# Power_ICs.net
KiCad netlist of a schematic drawn in Altium Designer
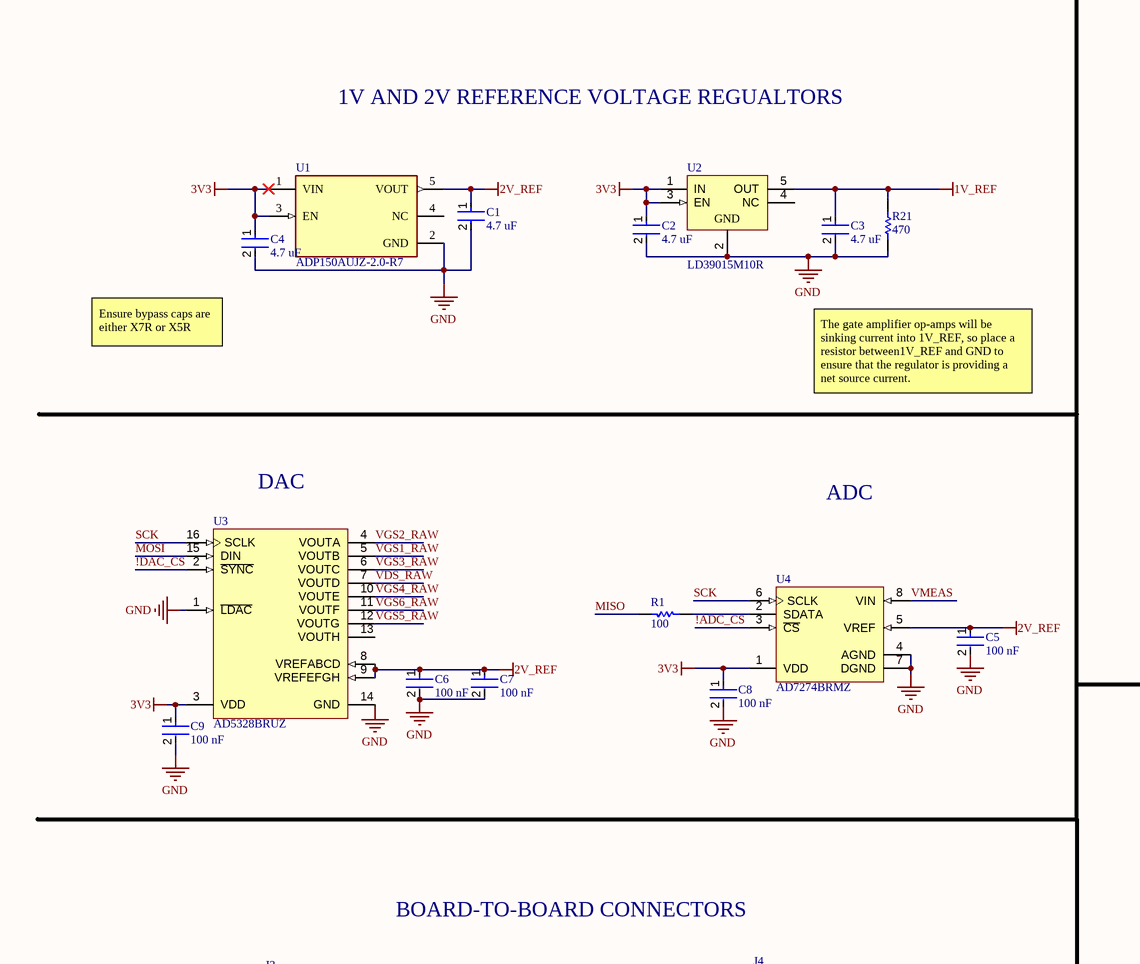
[diagram p0: Power+ICs.SchDoc, top left]
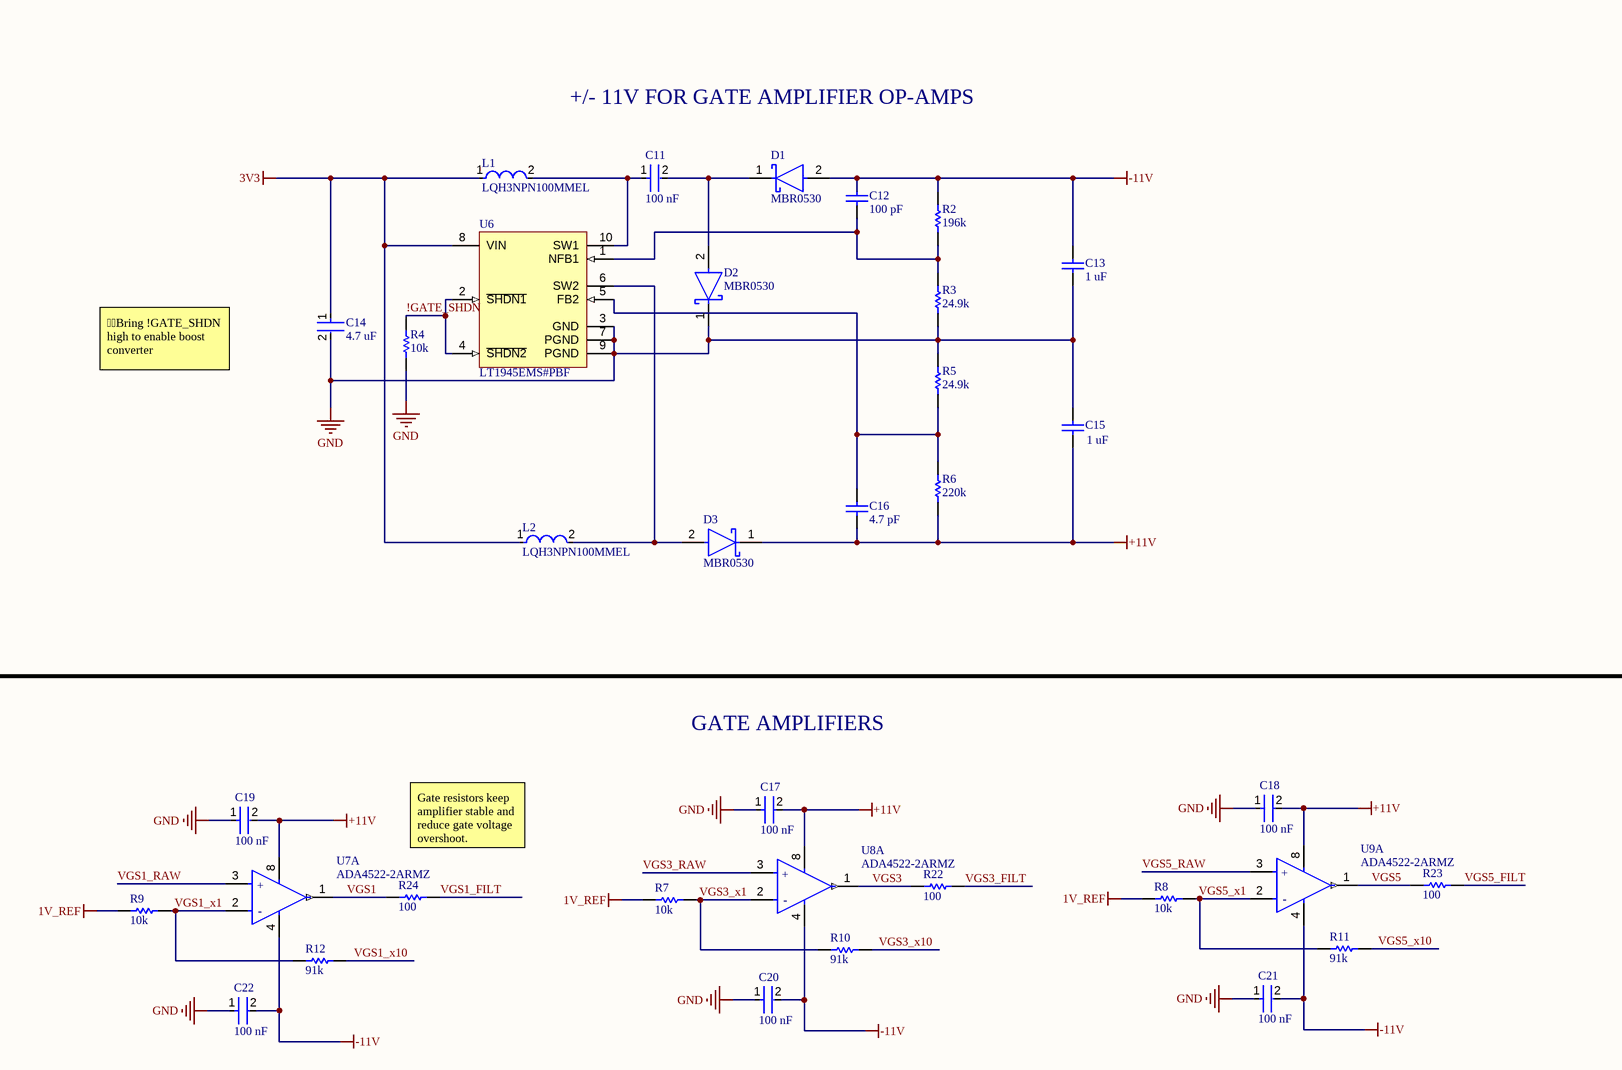
[diagram p1: Power+ICs.SchDoc, top right]
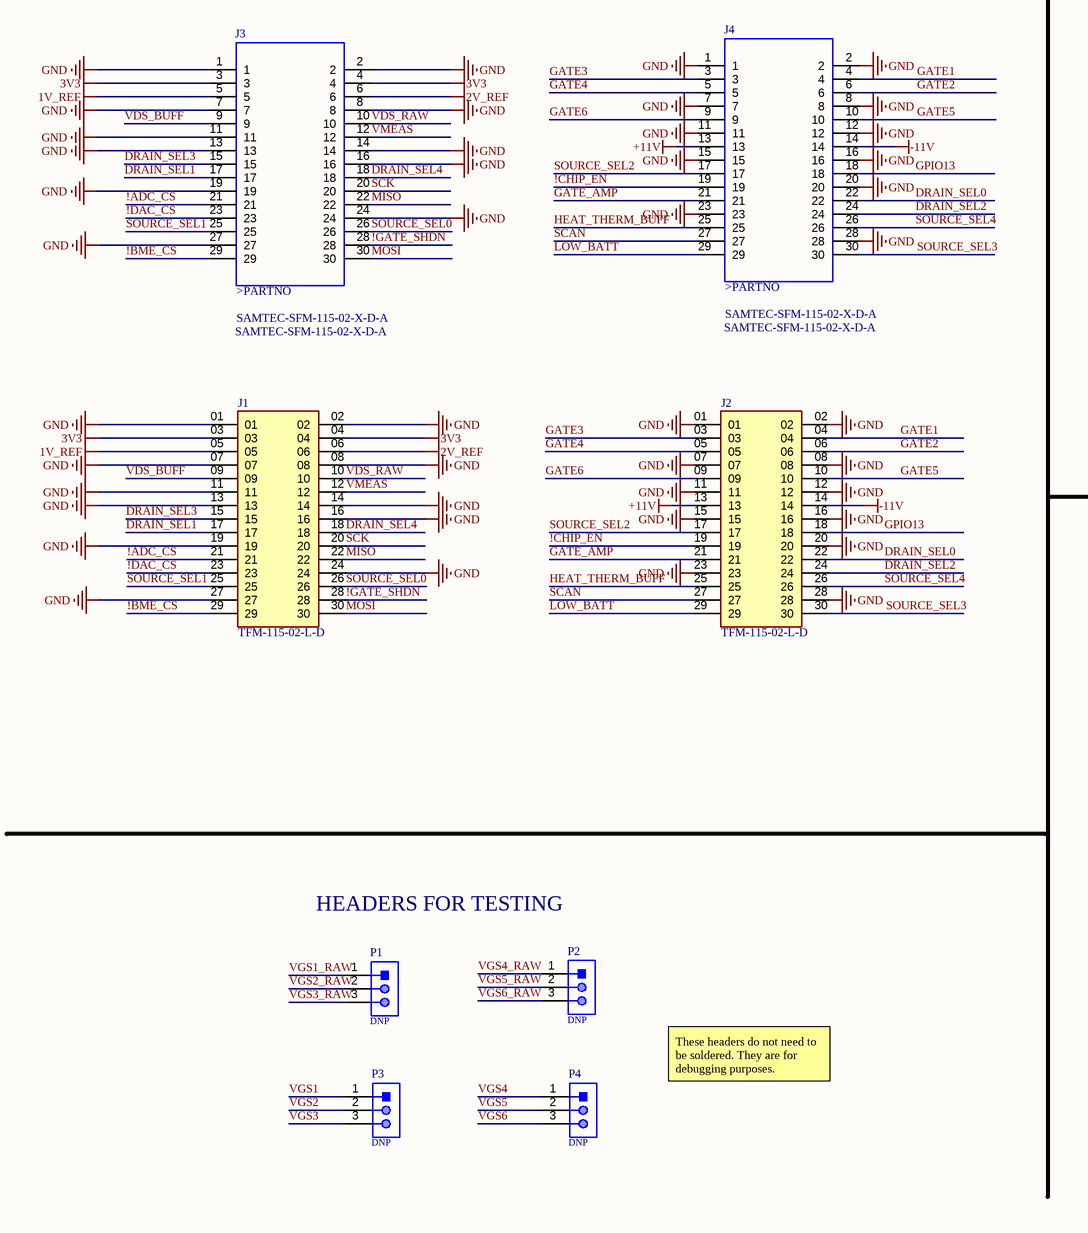
[diagram p2: Power+ICs.SchDoc, bottom left]
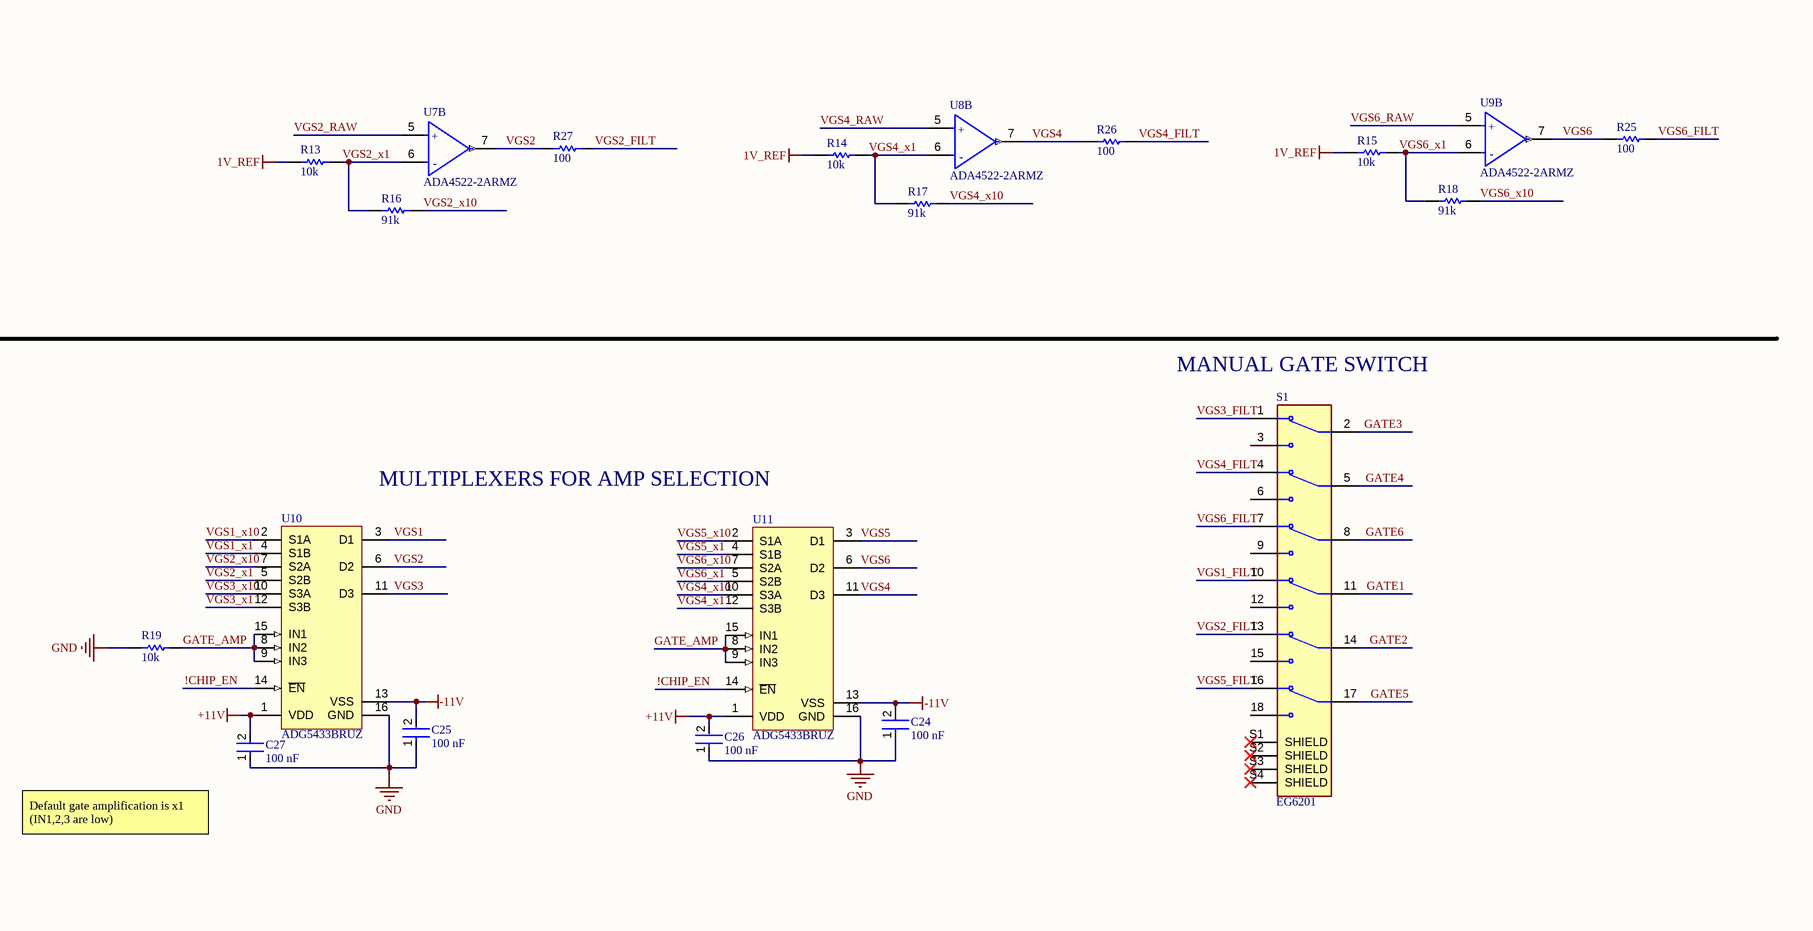
[diagram p3: Power+ICs.SchDoc, bottom right]

(export (version "E")
  (design (tool "Eeschema 10.0.6"))
  (components
    (comp (ref "C1")
      (value "4.7 uF")
      (footprint "FP-C0805C475K3PACTU-MFG")
      (description "CAP CER 4.7UF 25V X5R 0805")
      (fields (field (name "TOLERANCE") "10%") (field (name "VOLTAGE") "25V"))
      (libsource (lib "Altium Content Vault") (part "02cd4be3c70576c341d710602a673aa"))
    )
    (comp (ref "C2")
      (value "4.7 uF")
      (footprint "FP-C0805C475K3PACTU-MFG")
      (description "CAP CER 4.7UF 25V X5R 0805")
      (fields (field (name "TOLERANCE") "10%") (field (name "VOLTAGE") "25V"))
      (libsource (lib "Altium Content Vault") (part "02cd4be3c70576c341d710602a673aa"))
    )
    (comp (ref "C3")
      (value "4.7 uF")
      (footprint "FP-C0805C475K3PACTU-MFG")
      (description "CAP CER 4.7UF 25V X5R 0805")
      (fields (field (name "TOLERANCE") "10%") (field (name "VOLTAGE") "25V"))
      (libsource (lib "Altium Content Vault") (part "02cd4be3c70576c341d710602a673aa"))
    )
    (comp (ref "C4")
      (value "4.7 uF")
      (footprint "FP-C0805C475K3PACTU-MFG")
      (description "CAP CER 4.7UF 25V X5R 0805")
      (fields (field (name "TOLERANCE") "10%") (field (name "VOLTAGE") "25V"))
      (libsource (lib "Altium Content Vault") (part "02cd4be3c70576c341d710602a673aa"))
    )
    (comp (ref "C5")
      (value "100 nF")
      (footprint "FP-C0805C-DN-MFG")
      (description "CAP CER 0.1UF 50V X7R 0805")
      (fields
        (field (name "MANUFACTURER PART NUMBER") "C0805C104K5RACTU")
        (field (name "MANUFACTURER") "KEMET")
      )
      (libsource (lib "Altium Content Vault") (part "b4654b650e69147ec39a6b967a45e02"))
    )
    (comp (ref "C6")
      (value "100 nF")
      (footprint "FP-C0805C-DN-MFG")
      (description "CAP CER 0.1UF 50V X7R 0805")
      (fields
        (field (name "MANUFACTURER PART NUMBER") "C0805C104K5RACTU")
        (field (name "MANUFACTURER") "KEMET")
      )
      (libsource (lib "Altium Content Vault") (part "b4654b650e69147ec39a6b967a45e02"))
    )
    (comp (ref "C7")
      (value "100 nF")
      (footprint "FP-C0805C-DN-MFG")
      (description "CAP CER 0.1UF 50V X7R 0805")
      (fields
        (field (name "MANUFACTURER PART NUMBER") "C0805C104K5RACTU")
        (field (name "MANUFACTURER") "KEMET")
      )
      (libsource (lib "Altium Content Vault") (part "b4654b650e69147ec39a6b967a45e02"))
    )
    (comp (ref "C8")
      (value "100 nF")
      (footprint "FP-C0805C-DN-MFG")
      (description "CAP CER 0.1UF 50V X7R 0805")
      (fields
        (field (name "MANUFACTURER PART NUMBER") "C0805C104K5RACTU")
        (field (name "MANUFACTURER") "KEMET")
      )
      (libsource (lib "Altium Content Vault") (part "b4654b650e69147ec39a6b967a45e02"))
    )
    (comp (ref "C9")
      (value "100 nF")
      (footprint "FP-C0805C-DN-MFG")
      (description "CAP CER 0.1UF 50V X7R 0805")
      (fields
        (field (name "MANUFACTURER PART NUMBER") "C0805C104K5RACTU")
        (field (name "MANUFACTURER") "KEMET")
      )
      (libsource (lib "Altium Content Vault") (part "b4654b650e69147ec39a6b967a45e02"))
    )
    (comp (ref "C11")
      (value "100 nF")
      (footprint "FP-C0805C-DN-MFG")
      (description "CAP CER 0.1UF 50V X7R 0805")
      (fields
        (field (name "MANUFACTURER PART NUMBER") "C0805C104K5RACTU")
        (field (name "MANUFACTURER") "KEMET")
      )
      (libsource (lib "Altium Content Vault") (part "b4654b650e69147ec39a6b967a45e02"))
    )
    (comp (ref "C12")
      (value "100 pF")
      (footprint "CAPC2013X140X50ML20T25")
      (description "08055C101KAT2A")
      (fields (field (name "MANUFACTURER") "AVX Interconnect / Elco"))
      (libsource (lib "Altium Content Vault") (part "CAP"))
    )
    (comp (ref "C13")
      (value "1 uF")
      (footprint "CAPC3216X110X50LL20T25")
      (description "C1206C105K5RACTU")
      (fields (field (name "MANUFACTURER") "Kemet") (field (name "TOLERANCE") "10%"))
      (libsource (lib "Altium Content Vault") (part "CAP-NP-2"))
    )
    (comp (ref "C14")
      (value "4.7 uF")
      (footprint "FP-C0805C475K3PACTU-MFG")
      (description "CAP CER 4.7UF 25V X5R 0805")
      (fields (field (name "TOLERANCE") "10%") (field (name "VOLTAGE") "25V"))
      (libsource (lib "Altium Content Vault") (part "02cd4be3c70576c341d710602a673aa"))
    )
    (comp (ref "C15")
      (value "1 uF")
      (footprint "CAPC3216X110X50LL20T25")
      (description "C1206C105K5RACTU")
      (fields (field (name "MANUFACTURER") "Kemet") (field (name "TOLERANCE") "10%"))
      (libsource (lib "Altium Content Vault") (part "CAP-NP-2"))
    )
    (comp (ref "C16")
      (value "4.7 pF")
      (footprint "CAPC2013X71X50ML20T25")
      (description "08055A4R7CAT2A")
      (fields (field (name "MANUFACTURER") "AVX Interconnect / Elco"))
      (libsource (lib "Altium Content Vault") (part "CAP"))
    )
    (comp (ref "C17")
      (value "100 nF")
      (footprint "FP-C0805C-DN-MFG")
      (description "CAP CER 0.1UF 50V X7R 0805")
      (fields
        (field (name "MANUFACTURER PART NUMBER") "C0805C104K5RACTU")
        (field (name "MANUFACTURER") "KEMET")
      )
      (libsource (lib "Altium Content Vault") (part "b4654b650e69147ec39a6b967a45e02"))
    )
    (comp (ref "C18")
      (value "100 nF")
      (footprint "FP-C0805C-DN-MFG")
      (description "CAP CER 0.1UF 50V X7R 0805")
      (fields
        (field (name "MANUFACTURER PART NUMBER") "C0805C104K5RACTU")
        (field (name "MANUFACTURER") "KEMET")
      )
      (libsource (lib "Altium Content Vault") (part "b4654b650e69147ec39a6b967a45e02"))
    )
    (comp (ref "C19")
      (value "100 nF")
      (footprint "FP-C0805C-DN-MFG")
      (description "CAP CER 0.1UF 50V X7R 0805")
      (fields
        (field (name "MANUFACTURER PART NUMBER") "C0805C104K5RACTU")
        (field (name "MANUFACTURER") "KEMET")
      )
      (libsource (lib "Altium Content Vault") (part "b4654b650e69147ec39a6b967a45e02"))
    )
    (comp (ref "C20")
      (value "100 nF")
      (footprint "FP-C0805C-DN-MFG")
      (description "CAP CER 0.1UF 50V X7R 0805")
      (fields
        (field (name "MANUFACTURER PART NUMBER") "C0805C104K5RACTU")
        (field (name "MANUFACTURER") "KEMET")
      )
      (libsource (lib "Altium Content Vault") (part "b4654b650e69147ec39a6b967a45e02"))
    )
    (comp (ref "C21")
      (value "100 nF")
      (footprint "FP-C0805C-DN-MFG")
      (description "CAP CER 0.1UF 50V X7R 0805")
      (fields
        (field (name "MANUFACTURER PART NUMBER") "C0805C104K5RACTU")
        (field (name "MANUFACTURER") "KEMET")
      )
      (libsource (lib "Altium Content Vault") (part "b4654b650e69147ec39a6b967a45e02"))
    )
    (comp (ref "C22")
      (value "100 nF")
      (footprint "FP-C0805C-DN-MFG")
      (description "CAP CER 0.1UF 50V X7R 0805")
      (fields
        (field (name "MANUFACTURER PART NUMBER") "C0805C104K5RACTU")
        (field (name "MANUFACTURER") "KEMET")
      )
      (libsource (lib "Altium Content Vault") (part "b4654b650e69147ec39a6b967a45e02"))
    )
    (comp (ref "C24")
      (value "100 nF")
      (footprint "FP-C0805C-DN-MFG")
      (description "CAP CER 0.1UF 50V X7R 0805")
      (fields
        (field (name "MANUFACTURER PART NUMBER") "C0805C104K5RACTU")
        (field (name "MANUFACTURER") "KEMET")
      )
      (libsource (lib "Altium Content Vault") (part "b4654b650e69147ec39a6b967a45e02"))
    )
    (comp (ref "C25")
      (value "100 nF")
      (footprint "FP-C0805C-DN-MFG")
      (description "CAP CER 0.1UF 50V X7R 0805")
      (fields
        (field (name "MANUFACTURER PART NUMBER") "C0805C104K5RACTU")
        (field (name "MANUFACTURER") "KEMET")
      )
      (libsource (lib "Altium Content Vault") (part "b4654b650e69147ec39a6b967a45e02"))
    )
    (comp (ref "C26")
      (value "100 nF")
      (footprint "FP-C0805C-DN-MFG")
      (description "CAP CER 0.1UF 50V X7R 0805")
      (fields
        (field (name "MANUFACTURER PART NUMBER") "C0805C104K5RACTU")
        (field (name "MANUFACTURER") "KEMET")
      )
      (libsource (lib "Altium Content Vault") (part "b4654b650e69147ec39a6b967a45e02"))
    )
    (comp (ref "C27")
      (value "100 nF")
      (footprint "FP-C0805C-DN-MFG")
      (description "CAP CER 0.1UF 50V X7R 0805")
      (fields
        (field (name "MANUFACTURER PART NUMBER") "C0805C104K5RACTU")
        (field (name "MANUFACTURER") "KEMET")
      )
      (libsource (lib "Altium Content Vault") (part "b4654b650e69147ec39a6b967a45e02"))
    )
    (comp (ref "D1")
      (value "MBR0530")
      (footprint "FP-425-04-MFG")
      (description "DIODE SCHOTTKY 30V 500MA SOD123")
      (libsource (lib "Altium Content Vault") (part "1d6ec82d83fb6aee721767c19dac4b9"))
    )
    (comp (ref "D2")
      (value "MBR0530")
      (footprint "FP-425-04-MFG")
      (description "DIODE SCHOTTKY 30V 500MA SOD123")
      (libsource (lib "Altium Content Vault") (part "1d6ec82d83fb6aee721767c19dac4b9"))
    )
    (comp (ref "D3")
      (value "MBR0530")
      (footprint "FP-425-04-MFG")
      (description "DIODE SCHOTTKY 30V 500MA SOD123")
      (libsource (lib "Altium Content Vault") (part "1d6ec82d83fb6aee721767c19dac4b9"))
    )
    (comp (ref "J1")
      (value "TFM-115-02-L-D")
      (footprint "SAMTEC_TFM-115-02-L-D:SAMTEC_TFM-115-02-L-D")
      (fields (field (name "MF") "Samtec Inc."))
      (libsource (lib "TFM-115-02-L-D") (part "TFM-115-02-L-D"))
    )
    (comp (ref "J2")
      (value "TFM-115-02-L-D")
      (footprint "SAMTEC_TFM-115-02-L-D:SAMTEC_TFM-115-02-L-D")
      (fields (field (name "MF") "Samtec Inc."))
      (libsource (lib "TFM-115-02-L-D") (part "TFM-115-02-L-D"))
    )
    (comp (ref "J3")
      (value "SAMTEC-SFM-115-02-X-D-A")
      (footprint "SAMTEC-SFM-115-02-X-D-A:SAMTEC-SFM-115-02-X-D-A")
      (fields (field (name "MF") "Samtec Inc."))
      (libsource (lib "SAMTEC-SFM-115-02-X-D-A") (part "SAMTEC-SFM-115-02-X-D-A"))
    )
    (comp (ref "J4")
      (value "SAMTEC-SFM-115-02-X-D-A")
      (footprint "SAMTEC-SFM-115-02-X-D-A:SAMTEC-SFM-115-02-X-D-A")
      (fields (field (name "MF") "Samtec Inc."))
      (libsource (lib "SAMTEC-SFM-115-02-X-D-A") (part "SAMTEC-SFM-115-02-X-D-A"))
    )
    (comp (ref "L1")
      (value "LQH3NPN100MMEL")
      (footprint "FP-LQH3NPH_ME-MFG")
      (description "Wire Wound Ferrite Inductor for Power Lines 10μH ±20% 0.228Ω 1280mA 1212")
      (fields (field (name "TOLERANCE") "20%"))
      (libsource (lib "Altium Content Vault") (part "725321dda6339637d4d059423bc1c3c"))
    )
    (comp (ref "L2")
      (value "LQH3NPN100MMEL")
      (footprint "FP-LQH3NPH_ME-MFG")
      (description "Wire Wound Ferrite Inductor for Power Lines 10μH ±20% 0.228Ω 1280mA 1212")
      (fields (field (name "TOLERANCE") "20%"))
      (libsource (lib "Altium Content Vault") (part "725321dda6339637d4d059423bc1c3c"))
    )
    (comp (ref "P1")
      (value "DNP")
      (footprint "61300311021")
      (description "THT Angled Pin Header WR-PHD, Pitch 2.54 mm, Single Row, 3 pins")
      (fields
        (field (name "PART NUMBER") "61300311021")
        (field (name "MANUFACTURER") "Wurth Elektronik")
        (field (name "PUBLISHER") "WurthElektronik")
      )
      (libsource (lib "Altium Content Vault") (part "WE-CN-1P-M-R3"))
    )
    (comp (ref "P2")
      (value "DNP")
      (footprint "61300311021")
      (description "THT Angled Pin Header WR-PHD, Pitch 2.54 mm, Single Row, 3 pins")
      (fields
        (field (name "PART NUMBER") "61300311021")
        (field (name "MANUFACTURER") "Wurth Elektronik")
        (field (name "PUBLISHER") "WurthElektronik")
      )
      (libsource (lib "Altium Content Vault") (part "WE-CN-1P-M-R3"))
    )
    (comp (ref "P3")
      (value "DNP")
      (footprint "61300311021")
      (description "THT Angled Pin Header WR-PHD, Pitch 2.54 mm, Single Row, 3 pins")
      (fields
        (field (name "PART NUMBER") "61300311021")
        (field (name "MANUFACTURER") "Wurth Elektronik")
        (field (name "PUBLISHER") "WurthElektronik")
      )
      (libsource (lib "Altium Content Vault") (part "WE-CN-1P-M-R3"))
    )
    (comp (ref "P4")
      (value "DNP")
      (footprint "61300311021")
      (description "THT Angled Pin Header WR-PHD, Pitch 2.54 mm, Single Row, 3 pins")
      (fields
        (field (name "PART NUMBER") "61300311021")
        (field (name "MANUFACTURER") "Wurth Elektronik")
        (field (name "PUBLISHER") "WurthElektronik")
      )
      (libsource (lib "Altium Content Vault") (part "WE-CN-1P-M-R3"))
    )
    (comp (ref "R1")
      (value "100")
      (footprint "RESC2013X50X30LL20T20")
      (fields (field (name "MANUFACTURER") "Vishay Dale") (field (name "PART NUMBER") "CRCW0805100RFKEA"))
      (libsource (lib "Altium Content Vault") (part "RES"))
    )
    (comp (ref "R2")
      (value "196k")
      (footprint "RESC2013X50X30LL20T20")
      (fields (field (name "MANUFACTURER") "Vishay Dale") (field (name "PART NUMBER") "CRCW0805196KFKEA"))
      (libsource (lib "Altium Content Vault") (part "RES"))
    )
    (comp (ref "R3")
      (value "24.9k")
      (footprint "RESC2013X70X40LL20T20")
      (fields (field (name "PART NUMBER") "ERJ-6ENF2492V") (field (name "MANUFACTURER") "Panasonic"))
      (libsource (lib "Altium Content Vault") (part "RES"))
    )
    (comp (ref "R4")
      (value "10k")
      (footprint "RESC2013X60X35NL10T20")
      (description "Chip Resistor, 10 KOhm, +/- 1%, 0.125 W, -55 to 155 degC, 0805 (2012 Metric), RoHS, Tape and Reel")
      (fields (field (name "MANUFACTURER") "Yageo"))
      (libsource (lib "Altium Content Vault") (part "RES-2"))
    )
    (comp (ref "R5")
      (value "24.9k")
      (footprint "RESC2013X70X40LL20T20")
      (fields (field (name "PART NUMBER") "ERJ-6ENF2492V") (field (name "MANUFACTURER") "Panasonic"))
      (libsource (lib "Altium Content Vault") (part "RES"))
    )
    (comp (ref "R6")
      (value "220k")
      (footprint "RESC2013X70X40ML20T20")
      (fields (field (name "PART NUMBER") "ERJ6ENF2203V") (field (name "MANUFACTURER") "Panasonic"))
      (libsource (lib "Altium Content Vault") (part "RES"))
    )
    (comp (ref "R7")
      (value "10k")
      (footprint "RESC2013X60X35NL10T20")
      (description "Chip Resistor, 10 KOhm, +/- 1%, 0.125 W, -55 to 155 degC, 0805 (2012 Metric), RoHS, Tape and Reel")
      (fields (field (name "MANUFACTURER") "Yageo"))
      (libsource (lib "Altium Content Vault") (part "RES-2"))
    )
    (comp (ref "R8")
      (value "10k")
      (footprint "RESC2013X60X35NL10T20")
      (description "Chip Resistor, 10 KOhm, +/- 1%, 0.125 W, -55 to 155 degC, 0805 (2012 Metric), RoHS, Tape and Reel")
      (fields (field (name "MANUFACTURER") "Yageo"))
      (libsource (lib "Altium Content Vault") (part "RES-2"))
    )
    (comp (ref "R9")
      (value "10k")
      (footprint "RESC2013X60X35NL10T20")
      (description "Chip Resistor, 10 KOhm, +/- 1%, 0.125 W, -55 to 155 degC, 0805 (2012 Metric), RoHS, Tape and Reel")
      (fields (field (name "MANUFACTURER") "Yageo"))
      (libsource (lib "Altium Content Vault") (part "RES-2"))
    )
    (comp (ref "R10")
      (value "91k")
      (footprint "RESC2013X60X35ML10T20")
      (fields (field (name "PART NUMBER") "RC0805JR-0791KL") (field (name "MANUFACTURER") "Yageo"))
      (libsource (lib "Altium Content Vault") (part "RES"))
    )
    (comp (ref "R11")
      (value "91k")
      (footprint "RESC2013X60X35ML10T20")
      (fields (field (name "PART NUMBER") "RC0805JR-0791KL") (field (name "MANUFACTURER") "Yageo"))
      (libsource (lib "Altium Content Vault") (part "RES"))
    )
    (comp (ref "R12")
      (value "91k")
      (footprint "RESC2013X60X35ML10T20")
      (fields (field (name "PART NUMBER") "RC0805JR-0791KL") (field (name "MANUFACTURER") "Yageo"))
      (libsource (lib "Altium Content Vault") (part "RES"))
    )
    (comp (ref "R13")
      (value "10k")
      (footprint "RESC2013X60X35NL10T20")
      (description "Chip Resistor, 10 KOhm, +/- 1%, 0.125 W, -55 to 155 degC, 0805 (2012 Metric), RoHS, Tape and Reel")
      (fields (field (name "MANUFACTURER") "Yageo"))
      (libsource (lib "Altium Content Vault") (part "RES-2"))
    )
    (comp (ref "R14")
      (value "10k")
      (footprint "RESC2013X60X35NL10T20")
      (description "Chip Resistor, 10 KOhm, +/- 1%, 0.125 W, -55 to 155 degC, 0805 (2012 Metric), RoHS, Tape and Reel")
      (fields (field (name "MANUFACTURER") "Yageo"))
      (libsource (lib "Altium Content Vault") (part "RES-2"))
    )
    (comp (ref "R15")
      (value "10k")
      (footprint "RESC2013X60X35NL10T20")
      (description "Chip Resistor, 10 KOhm, +/- 1%, 0.125 W, -55 to 155 degC, 0805 (2012 Metric), RoHS, Tape and Reel")
      (fields (field (name "MANUFACTURER") "Yageo"))
      (libsource (lib "Altium Content Vault") (part "RES-2"))
    )
    (comp (ref "R16")
      (value "91k")
      (footprint "RESC2013X60X35ML10T20")
      (fields (field (name "PART NUMBER") "RC0805JR-0791KL") (field (name "MANUFACTURER") "Yageo"))
      (libsource (lib "Altium Content Vault") (part "RES"))
    )
    (comp (ref "R17")
      (value "91k")
      (footprint "RESC2013X60X35ML10T20")
      (fields (field (name "PART NUMBER") "RC0805JR-0791KL") (field (name "MANUFACTURER") "Yageo"))
      (libsource (lib "Altium Content Vault") (part "RES"))
    )
    (comp (ref "R18")
      (value "91k")
      (footprint "RESC2013X60X35ML10T20")
      (fields (field (name "PART NUMBER") "RC0805JR-0791KL") (field (name "MANUFACTURER") "Yageo"))
      (libsource (lib "Altium Content Vault") (part "RES"))
    )
    (comp (ref "R19")
      (value "10k")
      (footprint "RESC2013X60X35NL10T20")
      (description "Chip Resistor, 10 KOhm, +/- 1%, 0.125 W, -55 to 155 degC, 0805 (2012 Metric), RoHS, Tape and Reel")
      (fields (field (name "MANUFACTURER") "Yageo"))
      (libsource (lib "Altium Content Vault") (part "RES-2"))
    )
    (comp (ref "R21")
      (value "470")
      (footprint "RESC2013X70X40ML20T20")
      (description "Chip Resistor, 470 Ohm, +/- 1%, 0.125 W, -55 to 155 degC, 0805 (2012 Metric), RoHS, Tape and Reel")
      (fields (field (name "MANUFACTURER") "Panasonic"))
      (libsource (lib "Altium Content Vault") (part "RES-2"))
    )
    (comp (ref "R22")
      (value "100")
      (footprint "RESC2013X50X30LL20T20")
      (fields (field (name "MANUFACTURER") "Vishay Dale") (field (name "PART NUMBER") "CRCW0805100RFKEA"))
      (libsource (lib "Altium Content Vault") (part "RES"))
    )
    (comp (ref "R23")
      (value "100")
      (footprint "RESC2013X50X30LL20T20")
      (fields (field (name "MANUFACTURER") "Vishay Dale") (field (name "PART NUMBER") "CRCW0805100RFKEA"))
      (libsource (lib "Altium Content Vault") (part "RES"))
    )
    (comp (ref "R24")
      (value "100")
      (footprint "RESC2013X50X30LL20T20")
      (fields (field (name "MANUFACTURER") "Vishay Dale") (field (name "PART NUMBER") "CRCW0805100RFKEA"))
      (libsource (lib "Altium Content Vault") (part "RES"))
    )
    (comp (ref "R25")
      (value "100")
      (footprint "RESC2013X50X30LL20T20")
      (fields (field (name "MANUFACTURER") "Vishay Dale") (field (name "PART NUMBER") "CRCW0805100RFKEA"))
      (libsource (lib "Altium Content Vault") (part "RES"))
    )
    (comp (ref "R26")
      (value "100")
      (footprint "RESC2013X50X30LL20T20")
      (fields (field (name "MANUFACTURER") "Vishay Dale") (field (name "PART NUMBER") "CRCW0805100RFKEA"))
      (libsource (lib "Altium Content Vault") (part "RES"))
    )
    (comp (ref "R27")
      (value "100")
      (footprint "RESC2013X50X30LL20T20")
      (fields (field (name "MANUFACTURER") "Vishay Dale") (field (name "PART NUMBER") "CRCW0805100RFKEA"))
      (libsource (lib "Altium Content Vault") (part "RES"))
    )
    (comp (ref "S1")
      (value "EG6201")
      (footprint "SnapEDApcb:SW_EG6201")
      (description "Slide Switch 6PDT Through Hole, Right Angle")
      (fields (field (name "MF") "E-Switch"))
      (libsource (lib "SnapEDAsch") (part "EG6201"))
    )
    (comp (ref "U1")
      (value "ADP150AUJZ-2.0-R7")
      (footprint "FP-UJ-5-IPC_B")
      (description "IC REG LINEAR 2V 150MA 5TSOT")
      (libsource (lib "Altium Content Vault") (part "038a824adfd04a965d73cdd9fb88cf2"))
    )
    (comp (ref "U2")
      (value "LD39015M10R")
      (footprint "SOT23-5L_M")
      (description "150 mA Low Quiescent Current Low Noise Voltage Regulator, 1.0V, 5-Pin SOT-23, Tape and Reel")
      (libsource (lib "Altium Content Vault") (part "PM-REG-LD39015M-SOT5"))
    )
    (comp (ref "U3")
      (value "AD5328BRUZ")
      (footprint "RU-16_L")
      (fields (field (name "GENERIC PART NUMBER") "AD5328") (field (name "MANUFACTURER") "Analog Devices"))
      (libsource (lib "Altium Content Vault") (part "ADI-AD5328-RU-16"))
    )
    (comp (ref "U4")
      (value "AD7274BRMZ")
      (footprint "RM-8_N")
      (fields (field (name "GENERIC PART NUMBER") "AD7274") (field (name "MANUFACTURER") "Analog Devices"))
      (libsource (lib "Altium Content Vault") (part "ADI-AD7274-RM-8"))
    )
    (comp (ref "U6")
      (value "LT1945EMS#PBF")
      (footprint "LT-MS-10_N")
      (fields (field (name "MANUFACTURER") "Linear Technology"))
      (libsource (lib "Altium Content Vault") (part "LT-LT1945-MS-10"))
    )
    (comp (ref "U7")
      (value "ADA4522-2ARMZ")
      (footprint "FP-RM-8-IPC_C")
      (description "IC OPAMP ZERO-DRIFT 2 CIRC 8MSOP")
      (libsource (lib "Altium Content Vault") (part "e8c52d48d03680a0ba04c611cf3b55d"))
    )
    (comp (ref "U8")
      (value "ADA4522-2ARMZ")
      (footprint "FP-RM-8-IPC_C")
      (description "IC OPAMP ZERO-DRIFT 2 CIRC 8MSOP")
      (libsource (lib "Altium Content Vault") (part "e8c52d48d03680a0ba04c611cf3b55d"))
    )
    (comp (ref "U9")
      (value "ADA4522-2ARMZ")
      (footprint "FP-RM-8-IPC_C")
      (description "IC OPAMP ZERO-DRIFT 2 CIRC 8MSOP")
      (libsource (lib "Altium Content Vault") (part "e8c52d48d03680a0ba04c611cf3b55d"))
    )
    (comp (ref "U10")
      (value "ADG5433BRUZ")
      (footprint "ADI-RU-16_N")
      (description "High Voltage Latch-Up Proof, Triple SPDT Switches, 12.5 Ohm Ron, 16-pin SOP (RU-16), Tube")
      (fields (field (name "MANUFACTURER") "Analog Devices"))
      (libsource (lib "Altium Content Vault") (part "ADI-ADG5433-RU-16"))
    )
    (comp (ref "U11")
      (value "ADG5433BRUZ")
      (footprint "ADI-RU-16_N")
      (description "High Voltage Latch-Up Proof, Triple SPDT Switches, 12.5 Ohm Ron, 16-pin SOP (RU-16), Tube")
      (fields (field (name "MANUFACTURER") "Analog Devices"))
      (libsource (lib "Altium Content Vault") (part "ADI-ADG5433-RU-16"))
    )
  )
  (nets
    (net (code "1") (name "+11V") (class "Default")
      (node (ref "C15") (pin "1") (pinfunction "1_1") (pintype "passive"))
      (node (ref "C16") (pin "1") (pinfunction "1_1") (pintype "passive"))
      (node (ref "C17") (pin "2") (pinfunction "2_2") (pintype "passive"))
      (node (ref "C18") (pin "2") (pinfunction "2_2") (pintype "passive"))
      (node (ref "C19") (pin "2") (pinfunction "2_2") (pintype "passive"))
      (node (ref "C26") (pin "2") (pinfunction "2_2") (pintype "passive"))
      (node (ref "C27") (pin "2") (pinfunction "2_2") (pintype "passive"))
      (node (ref "D3") (pin "1") (pinfunction "C_1") (pintype "passive"))
      (node (ref "J2") (pin "13") (pinfunction "13_13") (pintype "passive"))
      (node (ref "J4") (pin "13") (pinfunction "13_13") (pintype "passive"))
      (node (ref "R6") (pin "1") (pinfunction "1_1") (pintype "passive"))
      (node (ref "U10") (pin "1") (pinfunction "VDD_1") (pintype "power_in"))
      (node (ref "U11") (pin "1") (pinfunction "VDD_1") (pintype "power_in"))
      (node (ref "U7") (pin "8") (pinfunction "V+_8") (pintype "power_in"))
      (node (ref "U8") (pin "8") (pinfunction "V+_8") (pintype "power_in"))
      (node (ref "U9") (pin "8") (pinfunction "V+_8") (pintype "power_in"))
    )
    (net (code "2") (name "-11V") (class "Default")
      (node (ref "C12") (pin "1") (pinfunction "1_1") (pintype "passive"))
      (node (ref "C13") (pin "2") (pinfunction "2_2") (pintype "passive"))
      (node (ref "C20") (pin "2") (pinfunction "2_2") (pintype "passive"))
      (node (ref "C21") (pin "2") (pinfunction "2_2") (pintype "passive"))
      (node (ref "C22") (pin "2") (pinfunction "2_2") (pintype "passive"))
      (node (ref "C24") (pin "2") (pinfunction "2_2") (pintype "passive"))
      (node (ref "C25") (pin "2") (pinfunction "2_2") (pintype "passive"))
      (node (ref "D1") (pin "2") (pinfunction "A_2") (pintype "passive"))
      (node (ref "J2") (pin "14") (pinfunction "14_14") (pintype "passive"))
      (node (ref "J4") (pin "14") (pinfunction "14_14") (pintype "passive"))
      (node (ref "R2") (pin "2") (pinfunction "2_2") (pintype "passive"))
      (node (ref "U10") (pin "13") (pinfunction "VSS_13") (pintype "power_in"))
      (node (ref "U11") (pin "13") (pinfunction "VSS_13") (pintype "power_in"))
      (node (ref "U7") (pin "4") (pinfunction "V-_4") (pintype "power_in"))
      (node (ref "U8") (pin "4") (pinfunction "V-_4") (pintype "power_in"))
      (node (ref "U9") (pin "4") (pinfunction "V-_4") (pintype "power_in"))
    )
    (net (code "3") (name "/!ADC_CS") (class "Default")
      (node (ref "J1") (pin "21") (pinfunction "21_21") (pintype "passive"))
      (node (ref "J3") (pin "21") (pinfunction "21_21") (pintype "passive"))
      (node (ref "U4") (pin "3") (pinfunction "~{CS}_3") (pintype "input"))
    )
    (net (code "4") (name "/!BME_CS") (class "Default")
      (node (ref "J1") (pin "29") (pinfunction "29_29") (pintype "passive"))
      (node (ref "J3") (pin "29") (pinfunction "29_29") (pintype "passive"))
    )
    (net (code "5") (name "/!CHIP_EN") (class "Default")
      (node (ref "J2") (pin "19") (pinfunction "19_19") (pintype "passive"))
      (node (ref "J4") (pin "19") (pinfunction "19_19") (pintype "passive"))
      (node (ref "U10") (pin "14") (pinfunction "~{EN}_14") (pintype "input"))
      (node (ref "U11") (pin "14") (pinfunction "~{EN}_14") (pintype "input"))
    )
    (net (code "6") (name "/!DAC_CS") (class "Default")
      (node (ref "J1") (pin "23") (pinfunction "23_23") (pintype "passive"))
      (node (ref "J3") (pin "23") (pinfunction "23_23") (pintype "passive"))
      (node (ref "U3") (pin "2") (pinfunction "~{SYNC}_2") (pintype "input"))
    )
    (net (code "7") (name "/!GATE_SHDN") (class "Default")
      (node (ref "J1") (pin "28") (pinfunction "28_28") (pintype "passive"))
      (node (ref "J3") (pin "28") (pinfunction "28_28") (pintype "passive"))
      (node (ref "R4") (pin "2") (pinfunction "2_2") (pintype "passive"))
      (node (ref "U6") (pin "2") (pinfunction "~{SHDN1}_2") (pintype "input"))
      (node (ref "U6") (pin "4") (pinfunction "~{SHDN2}_4") (pintype "input"))
    )
    (net (code "8") (name "/DRAIN_SEL0") (class "Default")
      (node (ref "J2") (pin "22") (pinfunction "22_22") (pintype "passive"))
      (node (ref "J4") (pin "22") (pinfunction "22_22") (pintype "passive"))
    )
    (net (code "9") (name "/DRAIN_SEL1") (class "Default")
      (node (ref "J1") (pin "17") (pinfunction "17_17") (pintype "passive"))
      (node (ref "J3") (pin "17") (pinfunction "17_17") (pintype "passive"))
    )
    (net (code "10") (name "/DRAIN_SEL2") (class "Default")
      (node (ref "J2") (pin "24") (pinfunction "24_24") (pintype "passive"))
      (node (ref "J4") (pin "24") (pinfunction "24_24") (pintype "passive"))
    )
    (net (code "11") (name "/DRAIN_SEL3") (class "Default")
      (node (ref "J1") (pin "15") (pinfunction "15_15") (pintype "passive"))
      (node (ref "J3") (pin "15") (pinfunction "15_15") (pintype "passive"))
    )
    (net (code "12") (name "/DRAIN_SEL4") (class "Default")
      (node (ref "J1") (pin "18") (pinfunction "18_18") (pintype "passive"))
      (node (ref "J3") (pin "18") (pinfunction "18_18") (pintype "passive"))
    )
    (net (code "13") (name "/GATE1") (class "Default")
      (node (ref "J2") (pin "04") (pinfunction "04_04") (pintype "passive"))
      (node (ref "J4") (pin "4") (pinfunction "4_4") (pintype "passive"))
      (node (ref "S1") (pin "11") (pinfunction "COM4_11") (pintype "passive"))
    )
    (net (code "14") (name "/GATE2") (class "Default")
      (node (ref "J2") (pin "06") (pinfunction "06_06") (pintype "passive"))
      (node (ref "J4") (pin "6") (pinfunction "6_6") (pintype "passive"))
      (node (ref "S1") (pin "14") (pinfunction "COM5_14") (pintype "passive"))
    )
    (net (code "15") (name "/GATE3") (class "Default")
      (node (ref "J2") (pin "03") (pinfunction "03_03") (pintype "passive"))
      (node (ref "J4") (pin "3") (pinfunction "3_3") (pintype "passive"))
      (node (ref "S1") (pin "2") (pinfunction "COM1_2") (pintype "passive"))
    )
    (net (code "16") (name "/GATE4") (class "Default")
      (node (ref "J2") (pin "05") (pinfunction "05_05") (pintype "passive"))
      (node (ref "J4") (pin "5") (pinfunction "5_5") (pintype "passive"))
      (node (ref "S1") (pin "5") (pinfunction "COM2_5") (pintype "passive"))
    )
    (net (code "17") (name "/GATE5") (class "Default")
      (node (ref "J2") (pin "10") (pinfunction "10_10") (pintype "passive"))
      (node (ref "J4") (pin "10") (pinfunction "10_10") (pintype "passive"))
      (node (ref "S1") (pin "17") (pinfunction "COM6_17") (pintype "passive"))
    )
    (net (code "18") (name "/GATE6") (class "Default")
      (node (ref "J2") (pin "09") (pinfunction "09_09") (pintype "passive"))
      (node (ref "J4") (pin "9") (pinfunction "9_9") (pintype "passive"))
      (node (ref "S1") (pin "8") (pinfunction "COM3_8") (pintype "passive"))
    )
    (net (code "19") (name "/GATE_AMP") (class "Default")
      (node (ref "J2") (pin "21") (pinfunction "21_21") (pintype "passive"))
      (node (ref "J4") (pin "21") (pinfunction "21_21") (pintype "passive"))
      (node (ref "R19") (pin "1") (pinfunction "1_1") (pintype "passive"))
      (node (ref "U10") (pin "15") (pinfunction "IN1_15") (pintype "input"))
      (node (ref "U10") (pin "8") (pinfunction "IN2_8") (pintype "input"))
      (node (ref "U10") (pin "9") (pinfunction "IN3_9") (pintype "input"))
      (node (ref "U11") (pin "15") (pinfunction "IN1_15") (pintype "input"))
      (node (ref "U11") (pin "8") (pinfunction "IN2_8") (pintype "input"))
      (node (ref "U11") (pin "9") (pinfunction "IN3_9") (pintype "input"))
    )
    (net (code "20") (name "/GPIO13") (class "Default")
      (node (ref "J2") (pin "18") (pinfunction "18_18") (pintype "passive"))
      (node (ref "J4") (pin "18") (pinfunction "18_18") (pintype "passive"))
    )
    (net (code "21") (name "/HEAT_THERM_BUFF") (class "Default")
      (node (ref "J2") (pin "25") (pinfunction "25_25") (pintype "passive"))
      (node (ref "J4") (pin "25") (pinfunction "25_25") (pintype "passive"))
    )
    (net (code "22") (name "/LOW_BATT") (class "Default")
      (node (ref "J2") (pin "29") (pinfunction "29_29") (pintype "passive"))
      (node (ref "J4") (pin "29") (pinfunction "29_29") (pintype "passive"))
    )
    (net (code "23") (name "/MISO") (class "Default")
      (node (ref "J1") (pin "22") (pinfunction "22_22") (pintype "passive"))
      (node (ref "J3") (pin "22") (pinfunction "22_22") (pintype "passive"))
      (node (ref "R1") (pin "2") (pinfunction "2_2") (pintype "passive"))
    )
    (net (code "24") (name "/MOSI") (class "Default")
      (node (ref "J1") (pin "30") (pinfunction "30_30") (pintype "passive"))
      (node (ref "J3") (pin "30") (pinfunction "30_30") (pintype "passive"))
      (node (ref "U3") (pin "15") (pinfunction "DIN_15") (pintype "input"))
    )
    (net (code "25") (name "/SCAN") (class "Default")
      (node (ref "J2") (pin "27") (pinfunction "27_27") (pintype "passive"))
      (node (ref "J4") (pin "27") (pinfunction "27_27") (pintype "passive"))
    )
    (net (code "26") (name "/SCK") (class "Default")
      (node (ref "J1") (pin "20") (pinfunction "20_20") (pintype "passive"))
      (node (ref "J3") (pin "20") (pinfunction "20_20") (pintype "passive"))
      (node (ref "U3") (pin "16") (pinfunction "SCLK_16") (pintype "input"))
      (node (ref "U4") (pin "6") (pinfunction "SCLK_6") (pintype "input"))
    )
    (net (code "27") (name "/SOURCE_SEL0") (class "Default")
      (node (ref "J1") (pin "26") (pinfunction "26_26") (pintype "passive"))
      (node (ref "J3") (pin "26") (pinfunction "26_26") (pintype "passive"))
    )
    (net (code "28") (name "/SOURCE_SEL1") (class "Default")
      (node (ref "J1") (pin "25") (pinfunction "25_25") (pintype "passive"))
      (node (ref "J3") (pin "25") (pinfunction "25_25") (pintype "passive"))
    )
    (net (code "29") (name "/SOURCE_SEL2") (class "Default")
      (node (ref "J2") (pin "17") (pinfunction "17_17") (pintype "passive"))
      (node (ref "J4") (pin "17") (pinfunction "17_17") (pintype "passive"))
    )
    (net (code "30") (name "/SOURCE_SEL3") (class "Default")
      (node (ref "J2") (pin "30") (pinfunction "30_30") (pintype "passive"))
      (node (ref "J4") (pin "30") (pinfunction "30_30") (pintype "passive"))
    )
    (net (code "31") (name "/SOURCE_SEL4") (class "Default")
      (node (ref "J2") (pin "26") (pinfunction "26_26") (pintype "passive"))
      (node (ref "J4") (pin "26") (pinfunction "26_26") (pintype "passive"))
    )
    (net (code "32") (name "/VDS_BUFF") (class "Default")
      (node (ref "J1") (pin "09") (pinfunction "09_09") (pintype "passive"))
      (node (ref "J3") (pin "9") (pinfunction "9_9") (pintype "passive"))
    )
    (net (code "33") (name "/VDS_RAW") (class "Default")
      (node (ref "J1") (pin "10") (pinfunction "10_10") (pintype "passive"))
      (node (ref "J3") (pin "10") (pinfunction "10_10") (pintype "passive"))
      (node (ref "U3") (pin "7") (pinfunction "VOUTD_7") (pintype "tri_state"))
    )
    (net (code "34") (name "/VGS1") (class "Default")
      (node (ref "P3") (pin "1") (pinfunction "1_1") (pintype "passive"))
      (node (ref "R24") (pin "1") (pinfunction "1_1") (pintype "passive"))
      (node (ref "U10") (pin "3") (pinfunction "D1_3") (pintype "passive"))
      (node (ref "U7") (pin "1") (pinfunction "OUT_A_1") (pintype "output"))
    )
    (net (code "35") (name "/VGS1_FILT") (class "Default")
      (node (ref "R24") (pin "2") (pinfunction "2_2") (pintype "passive"))
      (node (ref "S1") (pin "10") (pinfunction "NC4_10") (pintype "passive"))
    )
    (net (code "36") (name "/VGS1_RAW") (class "Default")
      (node (ref "P1") (pin "1") (pinfunction "1_1") (pintype "passive"))
      (node (ref "U3") (pin "5") (pinfunction "VOUTB_5") (pintype "tri_state"))
      (node (ref "U7") (pin "3") (pinfunction "+IN_A_3") (pintype "tri_state"))
    )
    (net (code "37") (name "/VGS1_x1") (class "Default")
      (node (ref "R12") (pin "1") (pinfunction "1_1") (pintype "passive"))
      (node (ref "R9") (pin "1") (pinfunction "1_1") (pintype "passive"))
      (node (ref "U10") (pin "4") (pinfunction "S1B_4") (pintype "passive"))
      (node (ref "U7") (pin "2") (pinfunction "-IN_A_2") (pintype "tri_state"))
    )
    (net (code "38") (name "/VGS1_x10") (class "Default")
      (node (ref "R12") (pin "2") (pinfunction "2_2") (pintype "passive"))
      (node (ref "U10") (pin "2") (pinfunction "S1A_2") (pintype "passive"))
    )
    (net (code "39") (name "/VGS2") (class "Default")
      (node (ref "P3") (pin "2") (pinfunction "2_2") (pintype "passive"))
      (node (ref "R27") (pin "1") (pinfunction "1_1") (pintype "passive"))
      (node (ref "U10") (pin "6") (pinfunction "D2_6") (pintype "passive"))
      (node (ref "U7") (pin "7") (pinfunction "OUT_B_7") (pintype "output"))
    )
    (net (code "40") (name "/VGS2_FILT") (class "Default")
      (node (ref "R27") (pin "2") (pinfunction "2_2") (pintype "passive"))
      (node (ref "S1") (pin "13") (pinfunction "NC5_13") (pintype "passive"))
    )
    (net (code "41") (name "/VGS2_RAW") (class "Default")
      (node (ref "P1") (pin "2") (pinfunction "2_2") (pintype "passive"))
      (node (ref "U3") (pin "4") (pinfunction "VOUTA_4") (pintype "tri_state"))
      (node (ref "U7") (pin "5") (pinfunction "+IN_B_5") (pintype "tri_state"))
    )
    (net (code "42") (name "/VGS2_x1") (class "Default")
      (node (ref "R13") (pin "1") (pinfunction "1_1") (pintype "passive"))
      (node (ref "R16") (pin "1") (pinfunction "1_1") (pintype "passive"))
      (node (ref "U10") (pin "5") (pinfunction "S2B_5") (pintype "passive"))
      (node (ref "U7") (pin "6") (pinfunction "-IN_B_6") (pintype "tri_state"))
    )
    (net (code "43") (name "/VGS2_x10") (class "Default")
      (node (ref "R16") (pin "2") (pinfunction "2_2") (pintype "passive"))
      (node (ref "U10") (pin "7") (pinfunction "S2A_7") (pintype "passive"))
    )
    (net (code "44") (name "/VGS3") (class "Default")
      (node (ref "P3") (pin "3") (pinfunction "3_3") (pintype "passive"))
      (node (ref "R22") (pin "1") (pinfunction "1_1") (pintype "passive"))
      (node (ref "U10") (pin "11") (pinfunction "D3_11") (pintype "passive"))
      (node (ref "U8") (pin "1") (pinfunction "OUT_A_1") (pintype "output"))
    )
    (net (code "45") (name "/VGS3_FILT") (class "Default")
      (node (ref "R22") (pin "2") (pinfunction "2_2") (pintype "passive"))
      (node (ref "S1") (pin "1") (pinfunction "NC1_1") (pintype "passive"))
    )
    (net (code "46") (name "/VGS3_RAW") (class "Default")
      (node (ref "P1") (pin "3") (pinfunction "3_3") (pintype "passive"))
      (node (ref "U3") (pin "6") (pinfunction "VOUTC_6") (pintype "tri_state"))
      (node (ref "U8") (pin "3") (pinfunction "+IN_A_3") (pintype "tri_state"))
    )
    (net (code "47") (name "/VGS3_x1") (class "Default")
      (node (ref "R10") (pin "1") (pinfunction "1_1") (pintype "passive"))
      (node (ref "R7") (pin "1") (pinfunction "1_1") (pintype "passive"))
      (node (ref "U10") (pin "12") (pinfunction "S3B_12") (pintype "passive"))
      (node (ref "U8") (pin "2") (pinfunction "-IN_A_2") (pintype "tri_state"))
    )
    (net (code "48") (name "/VGS3_x10") (class "Default")
      (node (ref "R10") (pin "2") (pinfunction "2_2") (pintype "passive"))
      (node (ref "U10") (pin "10") (pinfunction "S3A_10") (pintype "passive"))
    )
    (net (code "49") (name "/VGS4") (class "Default")
      (node (ref "P4") (pin "1") (pinfunction "1_1") (pintype "passive"))
      (node (ref "R26") (pin "1") (pinfunction "1_1") (pintype "passive"))
      (node (ref "U11") (pin "11") (pinfunction "D3_11") (pintype "passive"))
      (node (ref "U8") (pin "7") (pinfunction "OUT_B_7") (pintype "output"))
    )
    (net (code "50") (name "/VGS4_FILT") (class "Default")
      (node (ref "R26") (pin "2") (pinfunction "2_2") (pintype "passive"))
      (node (ref "S1") (pin "4") (pinfunction "NC2_4") (pintype "passive"))
    )
    (net (code "51") (name "/VGS4_RAW") (class "Default")
      (node (ref "P2") (pin "1") (pinfunction "1_1") (pintype "passive"))
      (node (ref "U3") (pin "10") (pinfunction "VOUTE_10") (pintype "tri_state"))
      (node (ref "U8") (pin "5") (pinfunction "+IN_B_5") (pintype "tri_state"))
    )
    (net (code "52") (name "/VGS4_x1") (class "Default")
      (node (ref "R14") (pin "1") (pinfunction "1_1") (pintype "passive"))
      (node (ref "R17") (pin "1") (pinfunction "1_1") (pintype "passive"))
      (node (ref "U11") (pin "12") (pinfunction "S3B_12") (pintype "passive"))
      (node (ref "U8") (pin "6") (pinfunction "-IN_B_6") (pintype "tri_state"))
    )
    (net (code "53") (name "/VGS4_x10") (class "Default")
      (node (ref "R17") (pin "2") (pinfunction "2_2") (pintype "passive"))
      (node (ref "U11") (pin "10") (pinfunction "S3A_10") (pintype "passive"))
    )
    (net (code "54") (name "/VGS5") (class "Default")
      (node (ref "P4") (pin "2") (pinfunction "2_2") (pintype "passive"))
      (node (ref "R23") (pin "1") (pinfunction "1_1") (pintype "passive"))
      (node (ref "U11") (pin "3") (pinfunction "D1_3") (pintype "passive"))
      (node (ref "U9") (pin "1") (pinfunction "OUT_A_1") (pintype "output"))
    )
    (net (code "55") (name "/VGS5_FILT") (class "Default")
      (node (ref "R23") (pin "2") (pinfunction "2_2") (pintype "passive"))
      (node (ref "S1") (pin "16") (pinfunction "NC6_16") (pintype "passive"))
    )
    (net (code "56") (name "/VGS5_RAW") (class "Default")
      (node (ref "P2") (pin "2") (pinfunction "2_2") (pintype "passive"))
      (node (ref "U3") (pin "12") (pinfunction "VOUTG_12") (pintype "tri_state"))
      (node (ref "U9") (pin "3") (pinfunction "+IN_A_3") (pintype "tri_state"))
    )
    (net (code "57") (name "/VGS5_x1") (class "Default")
      (node (ref "R11") (pin "1") (pinfunction "1_1") (pintype "passive"))
      (node (ref "R8") (pin "1") (pinfunction "1_1") (pintype "passive"))
      (node (ref "U11") (pin "4") (pinfunction "S1B_4") (pintype "passive"))
      (node (ref "U9") (pin "2") (pinfunction "-IN_A_2") (pintype "tri_state"))
    )
    (net (code "58") (name "/VGS5_x10") (class "Default")
      (node (ref "R11") (pin "2") (pinfunction "2_2") (pintype "passive"))
      (node (ref "U11") (pin "2") (pinfunction "S1A_2") (pintype "passive"))
    )
    (net (code "59") (name "/VGS6") (class "Default")
      (node (ref "P4") (pin "3") (pinfunction "3_3") (pintype "passive"))
      (node (ref "R25") (pin "1") (pinfunction "1_1") (pintype "passive"))
      (node (ref "U11") (pin "6") (pinfunction "D2_6") (pintype "passive"))
      (node (ref "U9") (pin "7") (pinfunction "OUT_B_7") (pintype "output"))
    )
    (net (code "60") (name "/VGS6_FILT") (class "Default")
      (node (ref "R25") (pin "2") (pinfunction "2_2") (pintype "passive"))
      (node (ref "S1") (pin "7") (pinfunction "NC3_7") (pintype "passive"))
    )
    (net (code "61") (name "/VGS6_RAW") (class "Default")
      (node (ref "P2") (pin "3") (pinfunction "3_3") (pintype "passive"))
      (node (ref "U3") (pin "11") (pinfunction "VOUTF_11") (pintype "tri_state"))
      (node (ref "U9") (pin "5") (pinfunction "+IN_B_5") (pintype "tri_state"))
    )
    (net (code "62") (name "/VGS6_x1") (class "Default")
      (node (ref "R15") (pin "1") (pinfunction "1_1") (pintype "passive"))
      (node (ref "R18") (pin "1") (pinfunction "1_1") (pintype "passive"))
      (node (ref "U11") (pin "5") (pinfunction "S2B_5") (pintype "passive"))
      (node (ref "U9") (pin "6") (pinfunction "-IN_B_6") (pintype "tri_state"))
    )
    (net (code "63") (name "/VGS6_x10") (class "Default")
      (node (ref "R18") (pin "2") (pinfunction "2_2") (pintype "passive"))
      (node (ref "U11") (pin "7") (pinfunction "S2A_7") (pintype "passive"))
    )
    (net (code "64") (name "/VMEAS") (class "Default")
      (node (ref "J1") (pin "12") (pinfunction "12_12") (pintype "passive"))
      (node (ref "J3") (pin "12") (pinfunction "12_12") (pintype "passive"))
      (node (ref "U4") (pin "8") (pinfunction "VIN_8") (pintype "input"))
    )
    (net (code "65") (name "1V_REF") (class "Default")
      (node (ref "C3") (pin "1") (pinfunction "1_1") (pintype "passive"))
      (node (ref "J1") (pin "05") (pinfunction "05_05") (pintype "passive"))
      (node (ref "J3") (pin "5") (pinfunction "5_5") (pintype "passive"))
      (node (ref "R13") (pin "2") (pinfunction "2_2") (pintype "passive"))
      (node (ref "R14") (pin "2") (pinfunction "2_2") (pintype "passive"))
      (node (ref "R15") (pin "2") (pinfunction "2_2") (pintype "passive"))
      (node (ref "R21") (pin "2") (pinfunction "2_2") (pintype "passive"))
      (node (ref "R7") (pin "2") (pinfunction "2_2") (pintype "passive"))
      (node (ref "R8") (pin "2") (pinfunction "2_2") (pintype "passive"))
      (node (ref "R9") (pin "2") (pinfunction "2_2") (pintype "passive"))
      (node (ref "U2") (pin "5") (pinfunction "OUT_5") (pintype "power_in"))
    )
    (net (code "66") (name "2V_REF") (class "Default")
      (node (ref "C1") (pin "1") (pinfunction "1_1") (pintype "passive"))
      (node (ref "C5") (pin "1") (pinfunction "1_1") (pintype "passive"))
      (node (ref "C6") (pin "1") (pinfunction "1_1") (pintype "passive"))
      (node (ref "C7") (pin "1") (pinfunction "1_1") (pintype "passive"))
      (node (ref "J1") (pin "06") (pinfunction "06_06") (pintype "passive"))
      (node (ref "J3") (pin "6") (pinfunction "6_6") (pintype "passive"))
      (node (ref "U1") (pin "5") (pinfunction "VOUT_5") (pintype "output"))
      (node (ref "U3") (pin "8") (pinfunction "VREFABCD_8") (pintype "input"))
      (node (ref "U3") (pin "9") (pinfunction "VREFEFGH_9") (pintype "input"))
      (node (ref "U4") (pin "5") (pinfunction "VREF_5") (pintype "input"))
    )
    (net (code "67") (name "3V3") (class "Default")
      (node (ref "C14") (pin "1") (pinfunction "1_1") (pintype "passive"))
      (node (ref "C2") (pin "1") (pinfunction "1_1") (pintype "passive"))
      (node (ref "C4") (pin "1") (pinfunction "1_1") (pintype "passive"))
      (node (ref "C8") (pin "1") (pinfunction "1_1") (pintype "passive"))
      (node (ref "C9") (pin "1") (pinfunction "1_1") (pintype "passive"))
      (node (ref "J1") (pin "03") (pinfunction "03_03") (pintype "passive"))
      (node (ref "J1") (pin "04") (pinfunction "04_04") (pintype "passive"))
      (node (ref "J3") (pin "3") (pinfunction "3_3") (pintype "passive"))
      (node (ref "J3") (pin "4") (pinfunction "4_4") (pintype "passive"))
      (node (ref "L1") (pin "1") (pinfunction "1_1") (pintype "passive"))
      (node (ref "L2") (pin "1") (pinfunction "1_1") (pintype "passive"))
      (node (ref "U1") (pin "1") (pinfunction "VIN_1") (pintype "tri_state"))
      (node (ref "U1") (pin "3") (pinfunction "EN_3") (pintype "input"))
      (node (ref "U2") (pin "1") (pinfunction "IN_1") (pintype "power_in"))
      (node (ref "U2") (pin "3") (pinfunction "EN_3") (pintype "input"))
      (node (ref "U3") (pin "3") (pinfunction "VDD_3") (pintype "power_in"))
      (node (ref "U4") (pin "1") (pinfunction "VDD_1") (pintype "power_in"))
      (node (ref "U6") (pin "8") (pinfunction "VIN_8") (pintype "power_in"))
    )
    (net (code "68") (name "GND") (class "Default")
      (node (ref "C1") (pin "2") (pinfunction "2_2") (pintype "passive"))
      (node (ref "C13") (pin "1") (pinfunction "1_1") (pintype "passive"))
      (node (ref "C14") (pin "2") (pinfunction "2_2") (pintype "passive"))
      (node (ref "C15") (pin "2") (pinfunction "2_2") (pintype "passive"))
      (node (ref "C17") (pin "1") (pinfunction "1_1") (pintype "passive"))
      (node (ref "C18") (pin "1") (pinfunction "1_1") (pintype "passive"))
      (node (ref "C19") (pin "1") (pinfunction "1_1") (pintype "passive"))
      (node (ref "C2") (pin "2") (pinfunction "2_2") (pintype "passive"))
      (node (ref "C20") (pin "1") (pinfunction "1_1") (pintype "passive"))
      (node (ref "C21") (pin "1") (pinfunction "1_1") (pintype "passive"))
      (node (ref "C22") (pin "1") (pinfunction "1_1") (pintype "passive"))
      (node (ref "C24") (pin "1") (pinfunction "1_1") (pintype "passive"))
      (node (ref "C25") (pin "1") (pinfunction "1_1") (pintype "passive"))
      (node (ref "C26") (pin "1") (pinfunction "1_1") (pintype "passive"))
      (node (ref "C27") (pin "1") (pinfunction "1_1") (pintype "passive"))
      (node (ref "C3") (pin "2") (pinfunction "2_2") (pintype "passive"))
      (node (ref "C4") (pin "2") (pinfunction "2_2") (pintype "passive"))
      (node (ref "C5") (pin "2") (pinfunction "2_2") (pintype "passive"))
      (node (ref "C6") (pin "2") (pinfunction "2_2") (pintype "passive"))
      (node (ref "C7") (pin "2") (pinfunction "2_2") (pintype "passive"))
      (node (ref "C8") (pin "2") (pinfunction "2_2") (pintype "passive"))
      (node (ref "C9") (pin "2") (pinfunction "2_2") (pintype "passive"))
      (node (ref "D2") (pin "1") (pinfunction "C_1") (pintype "passive"))
      (node (ref "J1") (pin "01") (pinfunction "01_01") (pintype "passive"))
      (node (ref "J1") (pin "02") (pinfunction "02_02") (pintype "passive"))
      (node (ref "J1") (pin "07") (pinfunction "07_07") (pintype "passive"))
      (node (ref "J1") (pin "08") (pinfunction "08_08") (pintype "passive"))
      (node (ref "J1") (pin "11") (pinfunction "11_11") (pintype "passive"))
      (node (ref "J1") (pin "13") (pinfunction "13_13") (pintype "passive"))
      (node (ref "J1") (pin "14") (pinfunction "14_14") (pintype "passive"))
      (node (ref "J1") (pin "16") (pinfunction "16_16") (pintype "passive"))
      (node (ref "J1") (pin "19") (pinfunction "19_19") (pintype "passive"))
      (node (ref "J1") (pin "24") (pinfunction "24_24") (pintype "passive"))
      (node (ref "J1") (pin "27") (pinfunction "27_27") (pintype "passive"))
      (node (ref "J2") (pin "01") (pinfunction "01_01") (pintype "passive"))
      (node (ref "J2") (pin "02") (pinfunction "02_02") (pintype "passive"))
      (node (ref "J2") (pin "07") (pinfunction "07_07") (pintype "passive"))
      (node (ref "J2") (pin "08") (pinfunction "08_08") (pintype "passive"))
      (node (ref "J2") (pin "11") (pinfunction "11_11") (pintype "passive"))
      (node (ref "J2") (pin "12") (pinfunction "12_12") (pintype "passive"))
      (node (ref "J2") (pin "15") (pinfunction "15_15") (pintype "passive"))
      (node (ref "J2") (pin "16") (pinfunction "16_16") (pintype "passive"))
      (node (ref "J2") (pin "20") (pinfunction "20_20") (pintype "passive"))
      (node (ref "J2") (pin "23") (pinfunction "23_23") (pintype "passive"))
      (node (ref "J2") (pin "28") (pinfunction "28_28") (pintype "passive"))
      (node (ref "J3") (pin "1") (pinfunction "1_1") (pintype "passive"))
      (node (ref "J3") (pin "11") (pinfunction "11_11") (pintype "passive"))
      (node (ref "J3") (pin "13") (pinfunction "13_13") (pintype "passive"))
      (node (ref "J3") (pin "14") (pinfunction "14_14") (pintype "passive"))
      (node (ref "J3") (pin "16") (pinfunction "16_16") (pintype "passive"))
      (node (ref "J3") (pin "19") (pinfunction "19_19") (pintype "passive"))
      (node (ref "J3") (pin "2") (pinfunction "2_2") (pintype "passive"))
      (node (ref "J3") (pin "24") (pinfunction "24_24") (pintype "passive"))
      (node (ref "J3") (pin "27") (pinfunction "27_27") (pintype "passive"))
      (node (ref "J3") (pin "7") (pinfunction "7_7") (pintype "passive"))
      (node (ref "J3") (pin "8") (pinfunction "8_8") (pintype "passive"))
      (node (ref "J4") (pin "1") (pinfunction "1_1") (pintype "passive"))
      (node (ref "J4") (pin "11") (pinfunction "11_11") (pintype "passive"))
      (node (ref "J4") (pin "12") (pinfunction "12_12") (pintype "passive"))
      (node (ref "J4") (pin "15") (pinfunction "15_15") (pintype "passive"))
      (node (ref "J4") (pin "16") (pinfunction "16_16") (pintype "passive"))
      (node (ref "J4") (pin "2") (pinfunction "2_2") (pintype "passive"))
      (node (ref "J4") (pin "20") (pinfunction "20_20") (pintype "passive"))
      (node (ref "J4") (pin "23") (pinfunction "23_23") (pintype "passive"))
      (node (ref "J4") (pin "28") (pinfunction "28_28") (pintype "passive"))
      (node (ref "J4") (pin "7") (pinfunction "7_7") (pintype "passive"))
      (node (ref "J4") (pin "8") (pinfunction "8_8") (pintype "passive"))
      (node (ref "R19") (pin "2") (pinfunction "2_2") (pintype "passive"))
      (node (ref "R21") (pin "1") (pinfunction "1_1") (pintype "passive"))
      (node (ref "R3") (pin "1") (pinfunction "1_1") (pintype "passive"))
      (node (ref "R4") (pin "1") (pinfunction "1_1") (pintype "passive"))
      (node (ref "R5") (pin "2") (pinfunction "2_2") (pintype "passive"))
      (node (ref "U1") (pin "2") (pinfunction "GND_2") (pintype "power_in"))
      (node (ref "U10") (pin "16") (pinfunction "GND_16") (pintype "power_in"))
      (node (ref "U11") (pin "16") (pinfunction "GND_16") (pintype "power_in"))
      (node (ref "U2") (pin "2") (pinfunction "GND_2") (pintype "power_in"))
      (node (ref "U3") (pin "1") (pinfunction "~{LDAC}_1") (pintype "input"))
      (node (ref "U3") (pin "14") (pinfunction "GND_14") (pintype "power_in"))
      (node (ref "U4") (pin "4") (pinfunction "AGND_4") (pintype "power_in"))
      (node (ref "U4") (pin "7") (pinfunction "DGND_7") (pintype "power_in"))
      (node (ref "U6") (pin "3") (pinfunction "GND_3") (pintype "power_in"))
      (node (ref "U6") (pin "7") (pinfunction "PGND_7") (pintype "power_in"))
      (node (ref "U6") (pin "9") (pinfunction "PGND_9") (pintype "power_in"))
    )
    (net (code "69") (name "Net-(D1-C)") (class "Default")
      (node (ref "C11") (pin "2") (pinfunction "2_2") (pintype "passive"))
      (node (ref "D1") (pin "1") (pinfunction "C_1") (pintype "passive"))
      (node (ref "D2") (pin "2") (pinfunction "A_2") (pintype "passive"))
    )
    (net (code "70") (name "Net-(D3-A)") (class "Default")
      (node (ref "D3") (pin "2") (pinfunction "A_2") (pintype "passive"))
      (node (ref "L2") (pin "2") (pinfunction "2_2") (pintype "passive"))
      (node (ref "U6") (pin "6") (pinfunction "SW2_6") (pintype "power_in"))
    )
    (net (code "71") (name "Net-(U4-SDATA)") (class "Default")
      (node (ref "R1") (pin "1") (pinfunction "1_1") (pintype "passive"))
      (node (ref "U4") (pin "2") (pinfunction "SDATA_2") (pintype "tri_state"))
    )
    (net (code "72") (name "Net-(U6-FB2)") (class "Default")
      (node (ref "C16") (pin "2") (pinfunction "2_2") (pintype "passive"))
      (node (ref "R5") (pin "1") (pinfunction "1_1") (pintype "passive"))
      (node (ref "R6") (pin "2") (pinfunction "2_2") (pintype "passive"))
      (node (ref "U6") (pin "5") (pinfunction "FB2_5") (pintype "input"))
    )
    (net (code "73") (name "Net-(U6-NFB1)") (class "Default")
      (node (ref "C12") (pin "2") (pinfunction "2_2") (pintype "passive"))
      (node (ref "R2") (pin "1") (pinfunction "1_1") (pintype "passive"))
      (node (ref "R3") (pin "2") (pinfunction "2_2") (pintype "passive"))
      (node (ref "U6") (pin "1") (pinfunction "NFB1_1") (pintype "input"))
    )
    (net (code "74") (name "Net-(U6-SW1)") (class "Default")
      (node (ref "C11") (pin "1") (pinfunction "1_1") (pintype "passive"))
      (node (ref "L1") (pin "2") (pinfunction "2_2") (pintype "passive"))
      (node (ref "U6") (pin "10") (pinfunction "SW1_10") (pintype "power_in"))
    )
    (net (code "75") (name "unconnected-(S1-NO1-Pad3)") (class "Default")
      (node (ref "S1") (pin "3") (pinfunction "NO1_3") (pintype "passive"))
    )
    (net (code "76") (name "unconnected-(S1-NO2-Pad6)") (class "Default")
      (node (ref "S1") (pin "6") (pinfunction "NO2_6") (pintype "passive"))
    )
    (net (code "77") (name "unconnected-(S1-NO3-Pad9)") (class "Default")
      (node (ref "S1") (pin "9") (pinfunction "NO3_9") (pintype "passive"))
    )
    (net (code "78") (name "unconnected-(S1-NO4-Pad12)") (class "Default")
      (node (ref "S1") (pin "12") (pinfunction "NO4_12") (pintype "passive"))
    )
    (net (code "79") (name "unconnected-(S1-NO5-Pad15)") (class "Default")
      (node (ref "S1") (pin "15") (pinfunction "NO5_15") (pintype "passive"))
    )
    (net (code "80") (name "unconnected-(S1-NO6-Pad18)") (class "Default")
      (node (ref "S1") (pin "18") (pinfunction "NO6_18") (pintype "passive"))
    )
    (net (code "81") (name "unconnected-(S1-SHIELD-PadS1)") (class "Default")
      (node (ref "S1") (pin "S1") (pinfunction "SHIELD_S1") (pintype "passive+no_connect"))
    )
    (net (code "82") (name "unconnected-(S1-SHIELD-PadS2)") (class "Default")
      (node (ref "S1") (pin "S2") (pinfunction "SHIELD_S2") (pintype "passive+no_connect"))
    )
    (net (code "83") (name "unconnected-(S1-SHIELD-PadS3)") (class "Default")
      (node (ref "S1") (pin "S3") (pinfunction "SHIELD_S3") (pintype "passive+no_connect"))
    )
    (net (code "84") (name "unconnected-(S1-SHIELD-PadS4)") (class "Default")
      (node (ref "S1") (pin "S4") (pinfunction "SHIELD_S4") (pintype "passive+no_connect"))
    )
    (net (code "85") (name "unconnected-(U1-NC-Pad4)") (class "Default")
      (node (ref "U1") (pin "4") (pinfunction "NC_4") (pintype "passive"))
    )
    (net (code "86") (name "unconnected-(U2-NC-Pad4)") (class "Default")
      (node (ref "U2") (pin "4") (pinfunction "NC_4") (pintype "passive"))
    )
    (net (code "87") (name "unconnected-(U3-VOUTH-Pad13)") (class "Default")
      (node (ref "U3") (pin "13") (pinfunction "VOUTH_13") (pintype "tri_state"))
    )
  )
)
